# WebCamLight_RevA.net
KiCad netlist of a schematic drawn in Altium Designer
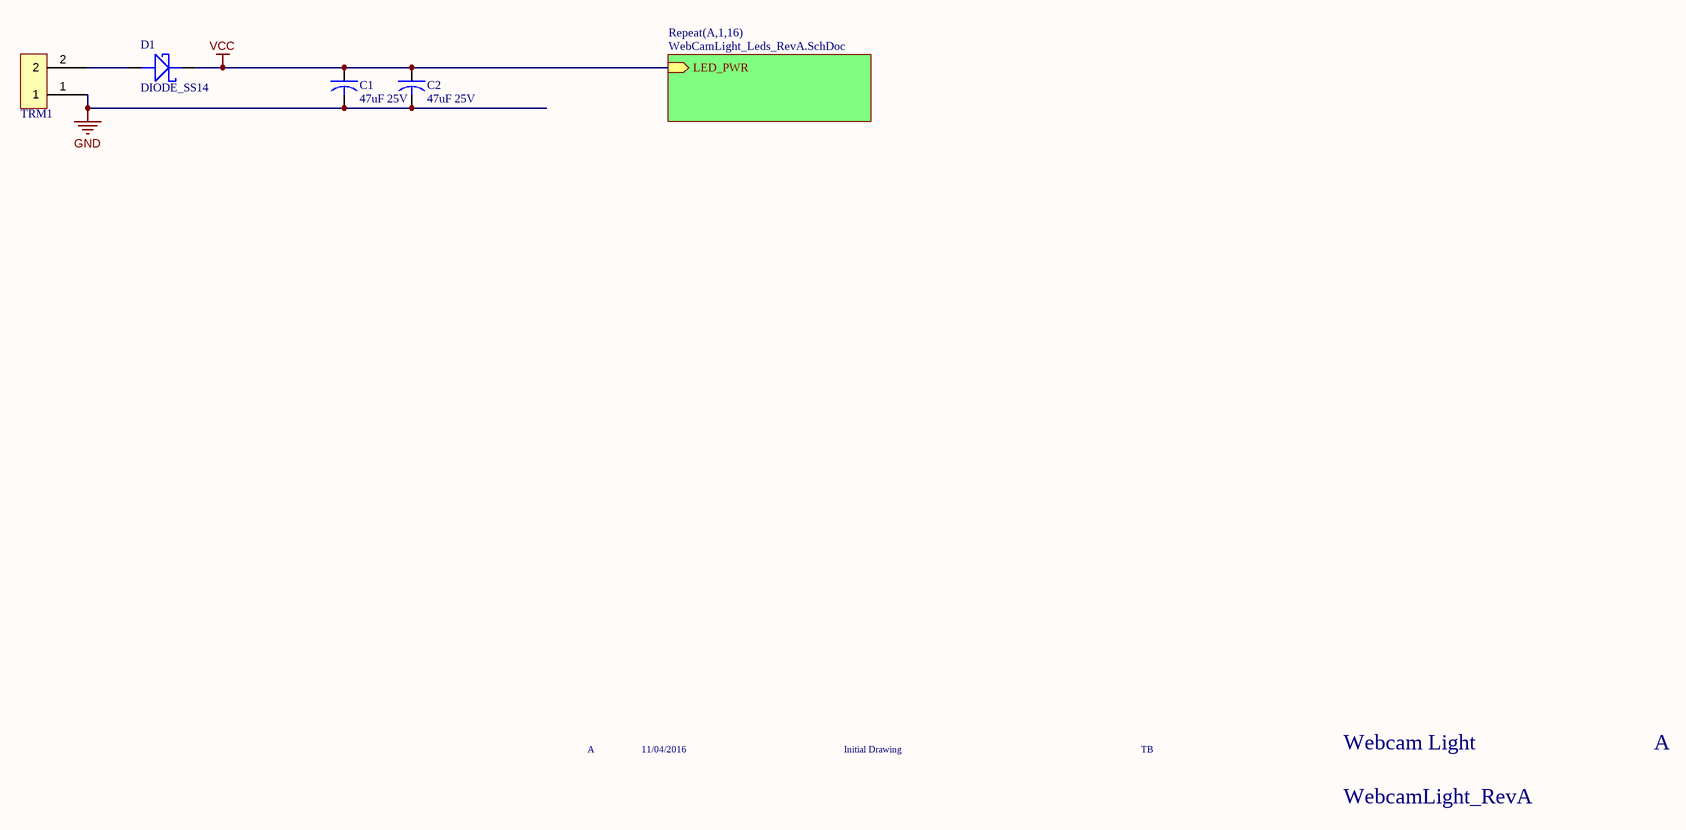
[diagram p0: WebCamLight_RevA.SchDoc]

(export (version "E")
  (design (tool "Eeschema 10.0.6"))
  (components
    (comp (ref "C1")
      (value "47uF 25V")
      (footprint "1206")
      (description "CAP CER 47uF 25V 20% X5R 1206")
      (fields (field (name "MANUFACTURER") "TDK Corporation"))
      (libsource (lib "Caps") (part "CAP_47uF_25V_20%_1206"))
    )
    (comp (ref "C2")
      (value "47uF 25V")
      (footprint "1206")
      (description "CAP CER 47uF 25V 20% X5R 1206")
      (fields (field (name "MANUFACTURER") "TDK Corporation"))
      (libsource (lib "Caps") (part "CAP_47uF_25V_20%_1206"))
    )
    (comp (ref "D1")
      (value "DIODE_SS14")
      (footprint "DO-214AC")
      (description "Schottky Diode, 1A, 40V SS14")
      (fields (field (name "MANUFACTURER") "Fairchild"))
      (libsource (lib "Semiconductors") (part "DIODE_SS14"))
    )
    (comp (ref "TRM1")
      (value "Wurth 2way screw terminal")
      (footprint "TERM_2POS_HORIZ_5.08MM")
      (description "TERM BLOCK 2POS HORIZ 5.08MM T/H")
      (fields (field (name "MANUFACTURER") "Wurth Electronics Inc"))
      (libsource (lib "Hardware") (part "TRM_2way_ScrewTerminal"))
    )
  )
  (nets
    (net (code "1") (name "GND") (class "Default")
      (node (ref "C1") (pin "2") (pinfunction "2_2") (pintype "passive"))
      (node (ref "C2") (pin "2") (pinfunction "2_2") (pintype "passive"))
      (node (ref "TRM1") (pin "1") (pinfunction "1_1") (pintype "tri_state"))
    )
    (net (code "2") (name "Net-(D1-PadA)") (class "Default")
      (node (ref "D1") (pin "A") (pinfunction "A_A") (pintype "passive"))
      (node (ref "TRM1") (pin "2") (pinfunction "2_2") (pintype "tri_state"))
    )
    (net (code "3") (name "VCC") (class "Default")
      (node (ref "C1") (pin "1") (pinfunction "1_1") (pintype "passive"))
      (node (ref "C2") (pin "1") (pinfunction "1_1") (pintype "passive"))
      (node (ref "D1") (pin "K") (pinfunction "K_K") (pintype "passive"))
    )
  )
)
